# VoltageLevelMeter3.net
KiCad netlist of a schematic drawn in EAGLE
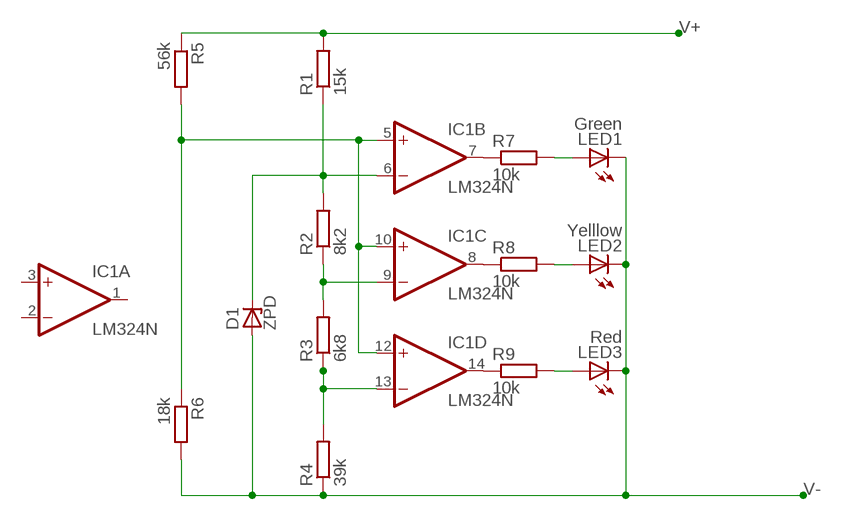
[diagram p0: schematic, sheet 1]

(export (version "E")
  (design (tool "Eeschema 10.0.6"))
  (components
    (comp (ref "D1")
      (value "ZPD")
      (footprint "eagle-import:DO35Z10")
      (libsource (lib "eagle-import") (part "ZPD"))
    )
    (comp (ref "IC1")
      (value "LM324N")
      (footprint "eagle-import:DIL14")
      (libsource (lib "eagle-import") (part "LM324N"))
    )
    (comp (ref "LED1")
      (value "Green")
      (footprint "eagle-import:LED3MM")
      (libsource (lib "eagle-import") (part "LED3MM"))
    )
    (comp (ref "LED2")
      (value "Yelllow")
      (footprint "eagle-import:LED3MM")
      (libsource (lib "eagle-import") (part "LED3MM"))
    )
    (comp (ref "LED3")
      (value "Red")
      (footprint "eagle-import:LED3MM")
      (libsource (lib "eagle-import") (part "LED3MM"))
    )
    (comp (ref "R1")
      (value "15k")
      (footprint "eagle-import:0207_7")
      (libsource (lib "eagle-import") (part "R-EU_0207/7"))
    )
    (comp (ref "R2")
      (value "8k2")
      (footprint "eagle-import:0207_7")
      (libsource (lib "eagle-import") (part "R-EU_0207/7"))
    )
    (comp (ref "R3")
      (value "6k8")
      (footprint "eagle-import:0207_7")
      (libsource (lib "eagle-import") (part "R-EU_0207/7"))
    )
    (comp (ref "R4")
      (value "39k")
      (footprint "eagle-import:0207_7")
      (libsource (lib "eagle-import") (part "R-EU_0207/7"))
    )
    (comp (ref "R5")
      (value "56k")
      (footprint "eagle-import:0207_7")
      (libsource (lib "eagle-import") (part "R-EU_0207/7"))
    )
    (comp (ref "R6")
      (value "18k")
      (footprint "eagle-import:0207_7")
      (libsource (lib "eagle-import") (part "R-EU_0207/7"))
    )
    (comp (ref "R7")
      (value "10k")
      (footprint "eagle-import:0207_7")
      (libsource (lib "eagle-import") (part "R-EU_0207/7"))
    )
    (comp (ref "R8")
      (value "10k")
      (footprint "eagle-import:0207_7")
      (libsource (lib "eagle-import") (part "R-EU_0207/7"))
    )
    (comp (ref "R9")
      (value "10k")
      (footprint "eagle-import:0207_7")
      (libsource (lib "eagle-import") (part "R-EU_0207/7"))
    )
  )
  (nets
    (net (code "1") (name "/V+") (class "Default")
      (node (ref "R1") (pin "2") (pinfunction "2_2") (pintype "passive"))
      (node (ref "R5") (pin "1") (pinfunction "1_1") (pintype "passive"))
    )
    (net (code "2") (name "/V-") (class "Default")
      (node (ref "D1") (pin "A") (pinfunction "A_A") (pintype "passive"))
      (node (ref "LED1") (pin "K") (pinfunction "C_K") (pintype "passive"))
      (node (ref "LED2") (pin "K") (pinfunction "C_K") (pintype "passive"))
      (node (ref "LED3") (pin "K") (pinfunction "C_K") (pintype "passive"))
      (node (ref "R4") (pin "1") (pinfunction "1_1") (pintype "passive"))
      (node (ref "R6") (pin "2") (pinfunction "2_2") (pintype "passive"))
    )
    (net (code "3") (name "Net-(IC1B-+IN)") (class "Default")
      (node (ref "IC1") (pin "10") (pinfunction "+IN_10") (pintype "input"))
      (node (ref "IC1") (pin "12") (pinfunction "+IN_12") (pintype "input"))
      (node (ref "IC1") (pin "5") (pinfunction "+IN_5") (pintype "input"))
      (node (ref "R5") (pin "2") (pinfunction "2_2") (pintype "passive"))
      (node (ref "R6") (pin "1") (pinfunction "1_1") (pintype "passive"))
    )
    (net (code "4") (name "Net-(IC1B--IN)") (class "Default")
      (node (ref "D1") (pin "C") (pinfunction "C_C") (pintype "passive"))
      (node (ref "IC1") (pin "6") (pinfunction "-IN_6") (pintype "input"))
      (node (ref "R1") (pin "1") (pinfunction "1_1") (pintype "passive"))
      (node (ref "R2") (pin "2") (pinfunction "2_2") (pintype "passive"))
    )
    (net (code "5") (name "Net-(IC1B-OUT)") (class "Default")
      (node (ref "IC1") (pin "7") (pinfunction "OUT_7") (pintype "output"))
      (node (ref "R7") (pin "1") (pinfunction "1_1") (pintype "passive"))
    )
    (net (code "6") (name "Net-(IC1C--IN)") (class "Default")
      (node (ref "IC1") (pin "9") (pinfunction "-IN_9") (pintype "input"))
      (node (ref "R2") (pin "1") (pinfunction "1_1") (pintype "passive"))
      (node (ref "R3") (pin "2") (pinfunction "2_2") (pintype "passive"))
    )
    (net (code "7") (name "Net-(IC1C-OUT)") (class "Default")
      (node (ref "IC1") (pin "8") (pinfunction "OUT_8") (pintype "output"))
      (node (ref "R8") (pin "1") (pinfunction "1_1") (pintype "passive"))
    )
    (net (code "8") (name "Net-(IC1D--IN)") (class "Default")
      (node (ref "IC1") (pin "13") (pinfunction "-IN_13") (pintype "input"))
      (node (ref "R3") (pin "1") (pinfunction "1_1") (pintype "passive"))
      (node (ref "R4") (pin "2") (pinfunction "2_2") (pintype "passive"))
    )
    (net (code "9") (name "Net-(IC1D-OUT)") (class "Default")
      (node (ref "IC1") (pin "14") (pinfunction "OUT_14") (pintype "output"))
      (node (ref "R9") (pin "1") (pinfunction "1_1") (pintype "passive"))
    )
    (net (code "10") (name "Net-(LED1-PadA)") (class "Default")
      (node (ref "LED1") (pin "A") (pinfunction "A_A") (pintype "passive"))
      (node (ref "R7") (pin "2") (pinfunction "2_2") (pintype "passive"))
    )
    (net (code "11") (name "Net-(LED2-PadA)") (class "Default")
      (node (ref "LED2") (pin "A") (pinfunction "A_A") (pintype "passive"))
      (node (ref "R8") (pin "2") (pinfunction "2_2") (pintype "passive"))
    )
    (net (code "12") (name "Net-(LED3-PadA)") (class "Default")
      (node (ref "LED3") (pin "A") (pinfunction "A_A") (pintype "passive"))
      (node (ref "R9") (pin "2") (pinfunction "2_2") (pintype "passive"))
    )
    (net (code "13") (name "unconnected-(IC1A-+IN-Pad3)") (class "Default")
      (node (ref "IC1") (pin "3") (pinfunction "+IN_3") (pintype "input"))
    )
    (net (code "14") (name "unconnected-(IC1A--IN-Pad2)") (class "Default")
      (node (ref "IC1") (pin "2") (pinfunction "-IN_2") (pintype "input"))
    )
    (net (code "15") (name "unconnected-(IC1A-OUT-Pad1)") (class "Default")
      (node (ref "IC1") (pin "1") (pinfunction "OUT_1") (pintype "output"))
    )
  )
)
